# Connectors.net
KiCad netlist of a schematic drawn in Altium Designer
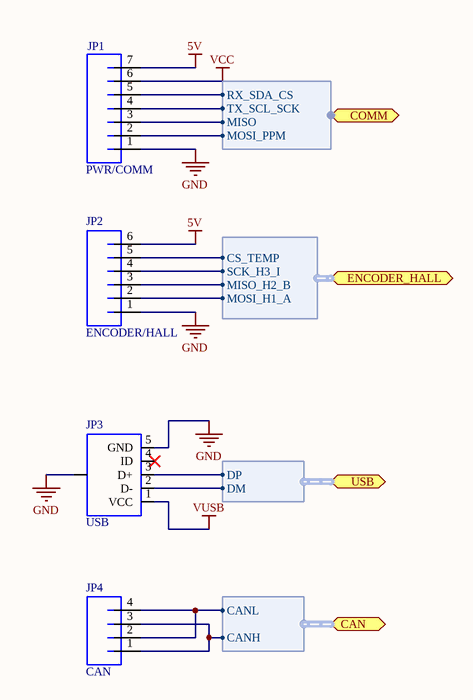
[diagram p0: Connectors.SchDoc]

(export (version "E")
  (design (tool "Eeschema 10.0.6"))
  (components
    (comp (ref "JP1")
      (value "PWR/COMM")
      (footprint "JST-PH-7-PTH-VERT")
      (fields
        (field (name "PARTNUMBER") "B7B-PH-K-S(LF)(SN)")
        (field (name "MANUFACTURER") "JST Sales America Inc.")
      )
      (libsource (lib "Connectors") (part "JST_PH_7_VERT"))
    )
    (comp (ref "JP2")
      (value "ENCODER/HALL")
      (footprint "JST-PH-6-PTH-VERT")
      (fields
        (field (name "PARTNUMBER") "B6B-PH-K-S(LF)(SN)")
        (field (name "MANUFACTURER") "JST Sales America Inc.")
      )
      (libsource (lib "Connectors") (part "JST_PH_6_VERT"))
    )
    (comp (ref "JP3")
      (value "USB")
      (footprint "USB-MICROB")
      (fields (field (name "PARTNUMBER") "10118192-0001LF") (field (name "MANUFACTURER") "Amphenol FCI"))
      (libsource (lib "Connectors-USB") (part "USB_MICROB_SMT"))
    )
    (comp (ref "JP4")
      (value "CAN")
      (footprint "JST-PH-4-PTH-VERT")
      (fields
        (field (name "PARTNUMBER") "B4B-PH-K-S(LF)(SN)")
        (field (name "MANUFACTURER") "JST Sales America Inc.")
      )
      (libsource (lib "Connectors") (part "JST_PH_4_VERT"))
    )
  )
  (nets
    (net (code "6") (name "/CANH") (class "Default")
      (node (ref "JP4") (pin "1") (pinfunction "1_1") (pintype "passive"))
      (node (ref "JP4") (pin "3") (pinfunction "3_3") (pintype "passive"))
    )
    (net (code "7") (name "/CANL") (class "Default")
      (node (ref "JP4") (pin "2") (pinfunction "2_2") (pintype "passive"))
      (node (ref "JP4") (pin "4") (pinfunction "4_4") (pintype "passive"))
    )
    (net (code "8") (name "/CS_TEMP") (class "Default")
      (node (ref "JP2") (pin "5") (pinfunction "5_5") (pintype "passive"))
    )
    (net (code "9") (name "/DM") (class "Default")
      (node (ref "JP3") (pin "2") (pinfunction "D-_2") (pintype "passive"))
    )
    (net (code "10") (name "/DP") (class "Default")
      (node (ref "JP3") (pin "3") (pinfunction "D+_3") (pintype "passive"))
    )
    (net (code "11") (name "/MISO") (class "Default")
      (node (ref "JP1") (pin "3") (pinfunction "3_3") (pintype "passive"))
    )
    (net (code "12") (name "/MISO_H2_B") (class "Default")
      (node (ref "JP2") (pin "3") (pinfunction "3_3") (pintype "passive"))
    )
    (net (code "13") (name "/MOSI_H1_A") (class "Default")
      (node (ref "JP2") (pin "2") (pinfunction "2_2") (pintype "passive"))
    )
    (net (code "14") (name "/MOSI_PPM") (class "Default")
      (node (ref "JP1") (pin "2") (pinfunction "2_2") (pintype "passive"))
    )
    (net (code "15") (name "/RX_SDA_CS") (class "Default")
      (node (ref "JP1") (pin "5") (pinfunction "5_5") (pintype "passive"))
    )
    (net (code "16") (name "/SCK_H3_I") (class "Default")
      (node (ref "JP2") (pin "4") (pinfunction "4_4") (pintype "passive"))
    )
    (net (code "17") (name "/TX_SCL_SCK") (class "Default")
      (node (ref "JP1") (pin "4") (pinfunction "4_4") (pintype "passive"))
    )
    (net (code "22") (name "5V") (class "Default")
      (node (ref "JP1") (pin "7") (pinfunction "7_7") (pintype "passive"))
      (node (ref "JP2") (pin "6") (pinfunction "6_6") (pintype "passive"))
    )
    (net (code "23") (name "GND") (class "Default")
      (node (ref "JP1") (pin "1") (pinfunction "1_1") (pintype "passive"))
      (node (ref "JP2") (pin "1") (pinfunction "1_1") (pintype "passive"))
      (node (ref "JP3") (pin "5") (pinfunction "GND_5") (pintype "passive"))
      (node (ref "JP3") (pin "6") (pinfunction "SHIELD_6") (pintype "passive"))
    )
    (net (code "24") (name "VCC") (class "Default")
      (node (ref "JP1") (pin "6") (pinfunction "6_6") (pintype "passive"))
    )
    (net (code "25") (name "VUSB") (class "Default")
      (node (ref "JP3") (pin "1") (pinfunction "VCC_1") (pintype "passive"))
    )
    (net (code "26") (name "unconnected-(JP3-ID-Pad4)") (class "Default")
      (node (ref "JP3") (pin "4") (pinfunction "ID_4") (pintype "passive+no_connect"))
    )
  )
)
